# peripheral.net
KiCad netlist of a schematic drawn in Altium Designer
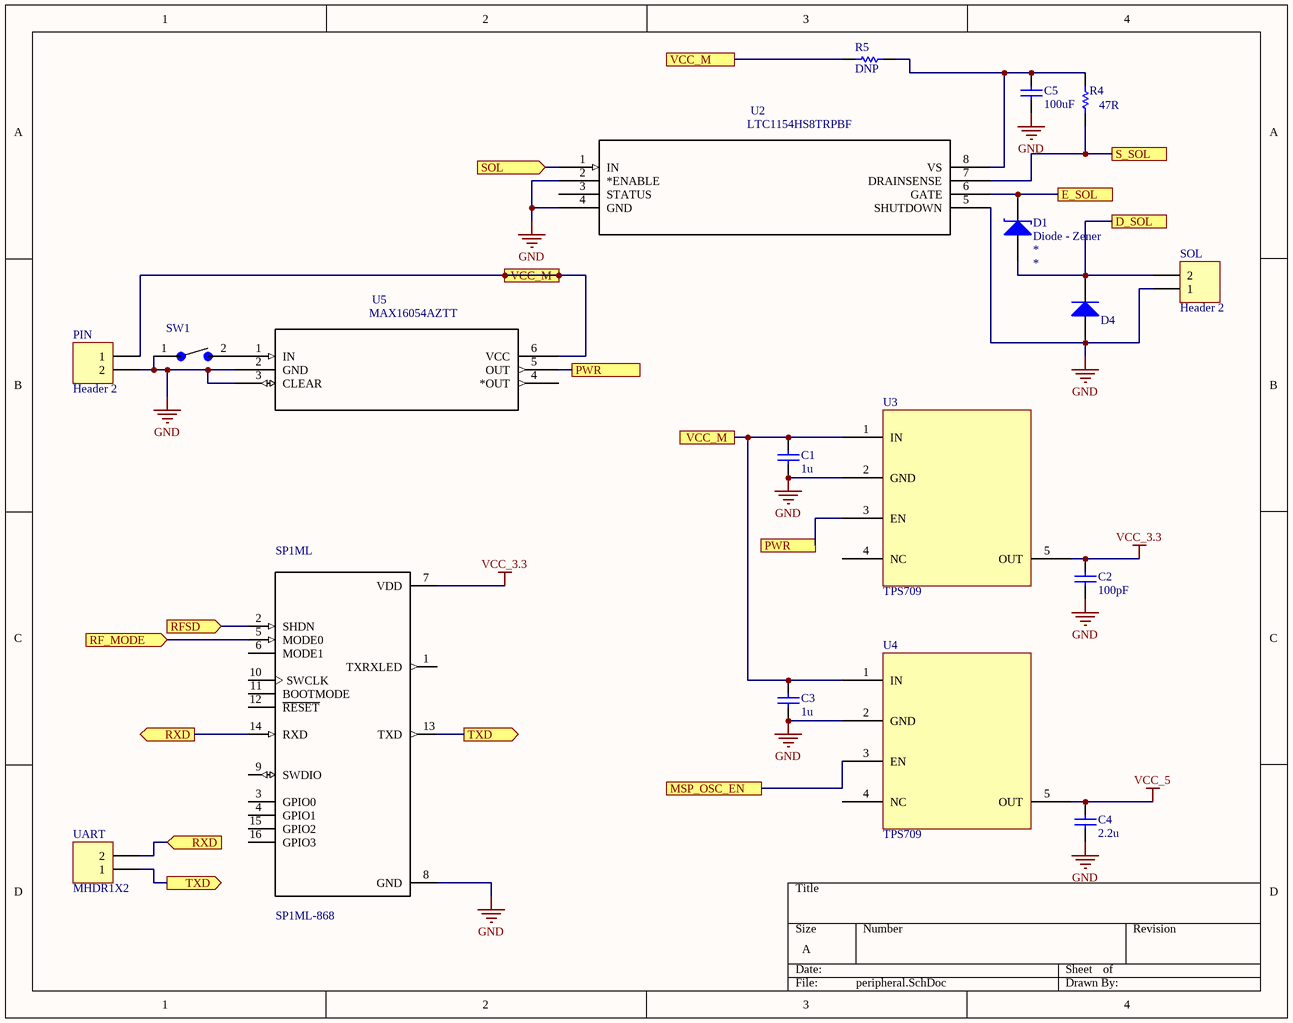
[diagram p0: peripheral.SchDoc]

(export (version "E")
  (design (tool "Eeschema 10.0.6"))
  (components
    (comp (ref "C1")
      (value "1u")
      (footprint "0402-W")
      (description "Ceramic Capacitor (Surface Mount)")
      (fields (field (name "MANUFACTURER") "Generic Ceramic Chip Cap (TBD)") (field (name "Comment") "Cap"))
      (libsource (lib "wisp") (part "Cap"))
    )
    (comp (ref "C2")
      (value "100pF")
      (footprint "0402-W")
      (description "Ceramic Capacitor (Surface Mount)")
      (fields (field (name "MANUFACTURER") "Generic Ceramic Chip Cap (TBD)") (field (name "Comment") "Cap"))
      (libsource (lib "wisp") (part "Cap"))
    )
    (comp (ref "C3")
      (value "1u")
      (footprint "0402-W")
      (description "Ceramic Capacitor (Surface Mount)")
      (fields (field (name "MANUFACTURER") "Generic Ceramic Chip Cap (TBD)") (field (name "Comment") "Cap"))
      (libsource (lib "wisp") (part "Cap"))
    )
    (comp (ref "C4")
      (value "2.2u")
      (footprint "0402-W")
      (description "Ceramic Capacitor (Surface Mount)")
      (fields (field (name "MANUFACTURER") "Generic Ceramic Chip Cap (TBD)") (field (name "Comment") "Cap"))
      (libsource (lib "wisp") (part "Cap"))
    )
    (comp (ref "C5")
      (value "100uF")
      (footprint "0402-W")
      (description "Ceramic Capacitor (Surface Mount)")
      (fields (field (name "MANUFACTURER") "Generic Ceramic Chip Cap (TBD)") (field (name "Comment") "Cap"))
      (libsource (lib "wisp") (part "Cap"))
    )
    (comp (ref "D1")
      (value "Diode - Zener")
      (footprint "SOD-523")
      (fields (field (name "ALTIUM_VALUE") "*") (field (name "RATING") "*"))
      (libsource (lib "wisp") (part "Diode - Zener"))
    )
    (comp (ref "D4")
      (value "Diode")
      (footprint "DIODE - SOD123")
      (description "General Purpose Diode")
      (libsource (lib "wisp") (part "Diode"))
    )
    (comp (ref "PIN")
      (value "Header 2")
      (footprint "HDR1X2")
      (description "Header, 2-Pin")
      (fields (field (name "PUBLISHER") "Altium Limited"))
      (libsource (lib "Miscellaneous Connectors") (part "Header 2"))
    )
    (comp (ref "R4")
      (value "47R")
      (footprint "0402")
      (description "Chip Resistor (Surface Mount)")
      (fields (field (name "MANUFACTURER") "Generic Chip Res (TBD)") (field (name "Comment") "R_Pullup_1"))
      (libsource (lib "WISP_AD10") (part "Res"))
    )
    (comp (ref "R5")
      (value "DNP")
      (footprint "0402")
      (description "Chip Resistor (Surface Mount)")
      (fields (field (name "MANUFACTURER") "Generic Chip Res (TBD)") (field (name "Comment") "R_Pullup_1"))
      (libsource (lib "WISP_AD10") (part "Res"))
    )
    (comp (ref "SOL")
      (value "Header 2")
      (footprint "HDR1X2")
      (description "Header, 2-Pin")
      (fields (field (name "PUBLISHER") "Altium Limited"))
      (libsource (lib "") (part "Header 2_1"))
    )
    (comp (ref "SP1ML")
      (value "SP1ML-868")
      (footprint "STM_SP1ML-868")
      (description "RF TXRX MODULE ISM<1GHZ CHIP ANT")
      (fields (field (name "MF") "STMicroelectronics"))
      (libsource (lib "SP1ML-868") (part "SP1ML-868"))
    )
    (comp (ref "SW1")
      (value "FSMSM _1437566-3_")
      (footprint "TE_FSMSM")
      (description "FSMSM=3.5X6 SMT TACT")
      (fields (field (name "MF") "TE Connectivity") (field (name "MP") "FSMSM"))
      (libsource (lib "FSMSM") (part "FSMSM"))
    )
    (comp (ref "U2")
      (value "LTC1154HS8TRPBF")
      (footprint "SOIC-8_S")
      (description "IC MOSFET DRIVER HIGH-SIDE 8SOIC")
      (fields (field (name "MF") "Linear Technology") (field (name "MP") "LTC1154HS8#TRPBF"))
      (libsource (lib "LTC1154HS8TRPBF") (part "LTC1154HS8TRPBF"))
    )
    (comp (ref "U3")
      (value "TPS709")
      (footprint "SOT95P280X145-5N")
      (description "Ultra low power Voltage Regulator")
      (libsource (lib "Fromm") (part "TPS709"))
    )
    (comp (ref "U4")
      (value "TPS709")
      (footprint "SOT95P280X145-5N")
      (description "Ultra low power Voltage Regulator")
      (libsource (lib "Fromm") (part "TPS709"))
    )
    (comp (ref "U5")
      (value "MAX16054AZTT")
      (footprint "21-0114C")
      (description "On/Off Controller With Debounce And +/-1")
      (fields (field (name "MF") "Maxim Integrated") (field (name "MP") "MAX16054AZT+"))
      (libsource (lib "MAX16054AZTT") (part "MAX16054AZTT"))
    )
    (comp (ref "UART")
      (value "MHDR1X2")
      (footprint "MHDR1X2")
      (description "Header, 2-Pin")
      (fields (field (name "PUBLISHER") "Altium Limited"))
      (libsource (lib "Miscellaneous Connectors") (part "MHDR1X2"))
    )
  )
  (nets
    (net (code "1") (name "/D_SOL") (class "Default")
      (node (ref "D1") (pin "1") (pinfunction "A_1") (pintype "passive"))
      (node (ref "D4") (pin "2") (pinfunction "C_2") (pintype "passive"))
      (node (ref "SOL") (pin "2") (pinfunction "2_2") (pintype "passive"))
    )
    (net (code "2") (name "/E_SOL") (class "Default")
      (node (ref "D1") (pin "2") (pinfunction "K_2") (pintype "passive"))
      (node (ref "U2") (pin "6") (pinfunction "GATE_6") (pintype "passive"))
    )
    (net (code "3") (name "/MSP_OSC_EN") (class "Default")
      (node (ref "U4") (pin "3") (pinfunction "EN_3") (pintype "passive"))
    )
    (net (code "4") (name "/PWR") (class "Default")
      (node (ref "U3") (pin "3") (pinfunction "EN_3") (pintype "passive"))
      (node (ref "U5") (pin "5") (pinfunction "OUT_5") (pintype "output"))
    )
    (net (code "5") (name "/RFSD") (class "Default")
      (node (ref "SP1ML") (pin "2") (pinfunction "SHDN_2") (pintype "input"))
    )
    (net (code "6") (name "/RF_MODE") (class "Default")
      (node (ref "SP1ML") (pin "5") (pinfunction "MODE0_5") (pintype "input"))
    )
    (net (code "7") (name "/RXD") (class "Default")
      (node (ref "SP1ML") (pin "14") (pinfunction "RXD_14") (pintype "input"))
      (node (ref "UART") (pin "2") (pinfunction "2_2") (pintype "passive"))
    )
    (net (code "8") (name "/SOL") (class "Default")
      (node (ref "U2") (pin "1") (pinfunction "IN_1") (pintype "input"))
    )
    (net (code "9") (name "/S_SOL") (class "Default")
      (node (ref "R4") (pin "1") (pinfunction "1_1") (pintype "passive"))
      (node (ref "U2") (pin "7") (pinfunction "DRAINSENSE_7") (pintype "passive"))
    )
    (net (code "10") (name "/TXD") (class "Default")
      (node (ref "SP1ML") (pin "13") (pinfunction "TXD_13") (pintype "output"))
      (node (ref "UART") (pin "1") (pinfunction "1_1") (pintype "passive"))
    )
    (net (code "11") (name "/VCC_M") (class "Default")
      (node (ref "C1") (pin "2") (pinfunction "2_2") (pintype "passive"))
      (node (ref "C3") (pin "2") (pinfunction "2_2") (pintype "passive"))
      (node (ref "PIN") (pin "1") (pinfunction "1_1") (pintype "passive"))
      (node (ref "R5") (pin "2") (pinfunction "2_2") (pintype "passive"))
      (node (ref "U3") (pin "1") (pinfunction "IN_1") (pintype "passive"))
      (node (ref "U4") (pin "1") (pinfunction "IN_1") (pintype "passive"))
      (node (ref "U5") (pin "6") (pinfunction "VCC_6") (pintype "power_in"))
    )
    (net (code "12") (name "GND") (class "Default")
      (node (ref "C1") (pin "1") (pinfunction "1_1") (pintype "passive"))
      (node (ref "C2") (pin "1") (pinfunction "1_1") (pintype "passive"))
      (node (ref "C3") (pin "1") (pinfunction "1_1") (pintype "passive"))
      (node (ref "C4") (pin "1") (pinfunction "1_1") (pintype "passive"))
      (node (ref "C5") (pin "1") (pinfunction "1_1") (pintype "passive"))
      (node (ref "D4") (pin "1") (pinfunction "A_1") (pintype "passive"))
      (node (ref "PIN") (pin "2") (pinfunction "2_2") (pintype "passive"))
      (node (ref "SOL") (pin "1") (pinfunction "1_1") (pintype "passive"))
      (node (ref "SP1ML") (pin "8") (pinfunction "GND_8") (pintype "passive"))
      (node (ref "SW1") (pin "1") (pinfunction "1_1") (pintype "passive"))
      (node (ref "U2") (pin "2") (pinfunction "*ENABLE_2") (pintype "passive"))
      (node (ref "U2") (pin "4") (pinfunction "GND_4") (pintype "power_in"))
      (node (ref "U2") (pin "5") (pinfunction "SHUTDOWN_5") (pintype "passive"))
      (node (ref "U3") (pin "2") (pinfunction "GND_2") (pintype "passive"))
      (node (ref "U4") (pin "2") (pinfunction "GND_2") (pintype "passive"))
      (node (ref "U5") (pin "2") (pinfunction "GND_2") (pintype "power_in"))
      (node (ref "U5") (pin "3") (pinfunction "CLEAR_3") (pintype "bidirectional"))
    )
    (net (code "13") (name "Net-(U2-VS)") (class "Default")
      (node (ref "C5") (pin "2") (pinfunction "2_2") (pintype "passive"))
      (node (ref "R4") (pin "2") (pinfunction "2_2") (pintype "passive"))
      (node (ref "R5") (pin "1") (pinfunction "1_1") (pintype "passive"))
      (node (ref "U2") (pin "8") (pinfunction "VS_8") (pintype "power_in"))
    )
    (net (code "14") (name "Net-(U5-IN)") (class "Default")
      (node (ref "SW1") (pin "2") (pinfunction "2_2") (pintype "passive"))
      (node (ref "U5") (pin "1") (pinfunction "IN_1") (pintype "input"))
    )
    (net (code "15") (name "VCC_3.3") (class "Default")
      (node (ref "C2") (pin "2") (pinfunction "2_2") (pintype "passive"))
      (node (ref "SP1ML") (pin "7") (pinfunction "VDD_7") (pintype "power_in"))
      (node (ref "U3") (pin "5") (pinfunction "OUT_5") (pintype "passive"))
    )
    (net (code "16") (name "VCC_5") (class "Default")
      (node (ref "C4") (pin "2") (pinfunction "2_2") (pintype "passive"))
      (node (ref "U4") (pin "5") (pinfunction "OUT_5") (pintype "passive"))
    )
    (net (code "17") (name "unconnected-(SP1ML-BOOTMODE-Pad11)") (class "Default")
      (node (ref "SP1ML") (pin "11") (pinfunction "BOOTMODE_11") (pintype "passive"))
    )
    (net (code "18") (name "unconnected-(SP1ML-GPIO0-Pad3)") (class "Default")
      (node (ref "SP1ML") (pin "3") (pinfunction "GPIO0_3") (pintype "passive"))
    )
    (net (code "19") (name "unconnected-(SP1ML-GPIO1-Pad4)") (class "Default")
      (node (ref "SP1ML") (pin "4") (pinfunction "GPIO1_4") (pintype "passive"))
    )
    (net (code "20") (name "unconnected-(SP1ML-GPIO2-Pad15)") (class "Default")
      (node (ref "SP1ML") (pin "15") (pinfunction "GPIO2_15") (pintype "passive"))
    )
    (net (code "21") (name "unconnected-(SP1ML-GPIO3-Pad16)") (class "Default")
      (node (ref "SP1ML") (pin "16") (pinfunction "GPIO3_16") (pintype "passive"))
    )
    (net (code "22") (name "unconnected-(SP1ML-MODE1-Pad6)") (class "Default")
      (node (ref "SP1ML") (pin "6") (pinfunction "MODE1_6") (pintype "passive"))
    )
    (net (code "23") (name "unconnected-(SP1ML-SWCLK-Pad10)") (class "Default")
      (node (ref "SP1ML") (pin "10") (pinfunction "SWCLK_10") (pintype "passive"))
    )
    (net (code "24") (name "unconnected-(SP1ML-SWDIO-Pad9)") (class "Default")
      (node (ref "SP1ML") (pin "9") (pinfunction "SWDIO_9") (pintype "bidirectional"))
    )
    (net (code "25") (name "unconnected-(SP1ML-TXRXLED-Pad1)") (class "Default")
      (node (ref "SP1ML") (pin "1") (pinfunction "TXRXLED_1") (pintype "output"))
    )
    (net (code "26") (name "unconnected-(SP1ML-~{RESET}-Pad12)") (class "Default")
      (node (ref "SP1ML") (pin "12") (pinfunction "~{RESET}_12") (pintype "passive"))
    )
    (net (code "27") (name "unconnected-(U2-STATUS-Pad3)") (class "Default")
      (node (ref "U2") (pin "3") (pinfunction "STATUS_3") (pintype "passive"))
    )
    (net (code "28") (name "unconnected-(U3-NC-Pad4)") (class "Default")
      (node (ref "U3") (pin "4") (pinfunction "NC_4") (pintype "passive"))
    )
    (net (code "29") (name "unconnected-(U4-NC-Pad4)") (class "Default")
      (node (ref "U4") (pin "4") (pinfunction "NC_4") (pintype "passive"))
    )
    (net (code "30") (name "unconnected-(U5-*OUT-Pad4)") (class "Default")
      (node (ref "U5") (pin "4") (pinfunction "*OUT_4") (pintype "output"))
    )
  )
)
